# Main.net
KiCad netlist of a schematic drawn in Altium Designer
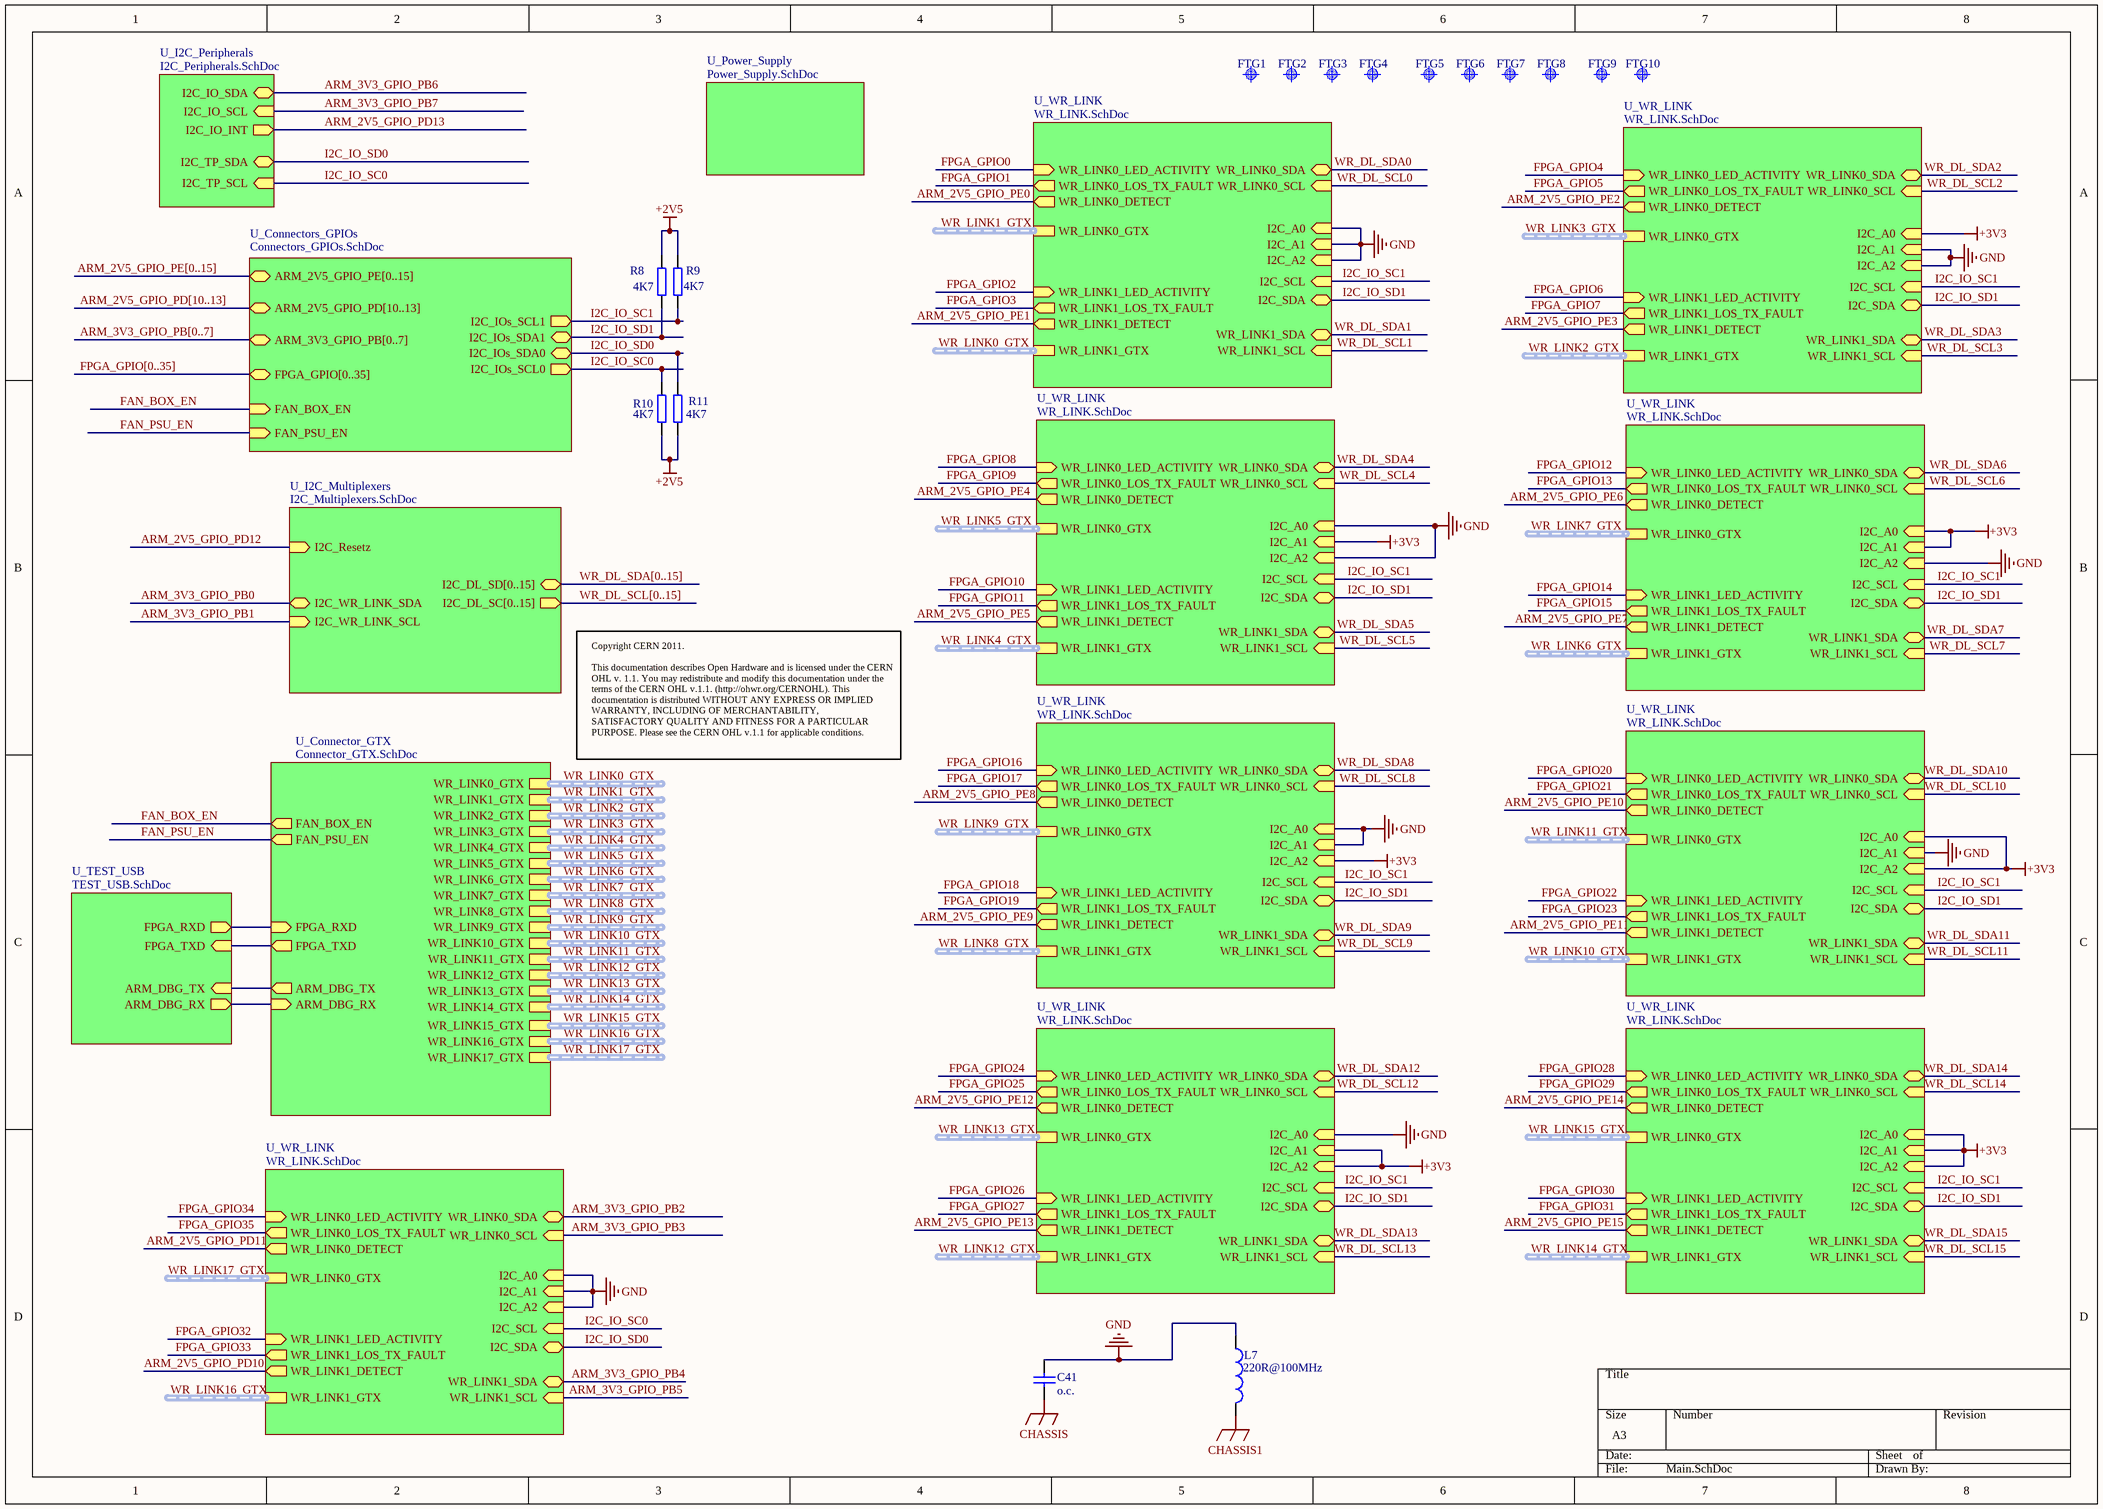
[diagram p0: Main.SchDoc]

(export (version "E")
  (design (tool "Eeschema 10.0.6"))
  (components
    (comp (ref "C41")
      (value "o.c.")
      (footprint "CC1608-0603")
      (description "Capacitor")
      (fields
        (field (name "TOLERANCE") "±10%")
        (field (name "VOLTAGE") "16V")
        (field (name "PUBLISHER") "Altium Limited")
      )
      (libsource (lib "wr_switch") (part "Cap"))
    )
    (comp (ref "FTG1")
      (value "Use only in PCB")
      (footprint "FIDUCIAL_TOP_S100-200")
      (description "Fiducial Target")
      (fields (field (name "PART NUMBER") "FIDUCIAL_TARGET_S100-200") (field (name "AUTHOR") "CERN DEM JLC"))
      (libsource (lib "wr_switch") (part "Fiducial Target"))
    )
    (comp (ref "FTG2")
      (value "Use only in PCB")
      (footprint "FIDUCIAL_TOP_S100-200")
      (description "Fiducial Target")
      (fields (field (name "PART NUMBER") "FIDUCIAL_TARGET_S100-200") (field (name "AUTHOR") "CERN DEM JLC"))
      (libsource (lib "wr_switch") (part "Fiducial Target"))
    )
    (comp (ref "FTG3")
      (value "Use only in PCB")
      (footprint "FIDUCIAL_TOP_S100-200")
      (description "Fiducial Target")
      (fields (field (name "PART NUMBER") "FIDUCIAL_TARGET_S100-200") (field (name "AUTHOR") "CERN DEM JLC"))
      (libsource (lib "wr_switch") (part "Fiducial Target"))
    )
    (comp (ref "FTG4")
      (value "Use only in PCB")
      (footprint "FIDUCIAL_TOP_S100-200")
      (description "Fiducial Target")
      (fields (field (name "PART NUMBER") "FIDUCIAL_TARGET_S100-200") (field (name "AUTHOR") "CERN DEM JLC"))
      (libsource (lib "wr_switch") (part "Fiducial Target"))
    )
    (comp (ref "FTG5")
      (value "Use only in PCB")
      (footprint "FIDUCIAL_TOP_S100-200")
      (description "Fiducial Target")
      (fields (field (name "PART NUMBER") "FIDUCIAL_TARGET_S100-200") (field (name "AUTHOR") "CERN DEM JLC"))
      (libsource (lib "wr_switch") (part "Fiducial Target"))
    )
    (comp (ref "FTG6")
      (value "Use only in PCB")
      (footprint "FIDUCIAL_TOP_S100-200")
      (description "Fiducial Target")
      (fields (field (name "PART NUMBER") "FIDUCIAL_TARGET_S100-200") (field (name "AUTHOR") "CERN DEM JLC"))
      (libsource (lib "wr_switch") (part "Fiducial Target"))
    )
    (comp (ref "FTG7")
      (value "Use only in PCB")
      (footprint "FIDUCIAL_TOP_S100-200")
      (description "Fiducial Target")
      (fields (field (name "PART NUMBER") "FIDUCIAL_TARGET_S100-200") (field (name "AUTHOR") "CERN DEM JLC"))
      (libsource (lib "wr_switch") (part "Fiducial Target"))
    )
    (comp (ref "FTG8")
      (value "Use only in PCB")
      (footprint "FIDUCIAL_TOP_S100-200")
      (description "Fiducial Target")
      (fields (field (name "PART NUMBER") "FIDUCIAL_TARGET_S100-200") (field (name "AUTHOR") "CERN DEM JLC"))
      (libsource (lib "wr_switch") (part "Fiducial Target"))
    )
    (comp (ref "FTG9")
      (value "Use only in PCB")
      (footprint "FIDUCIAL_TOP_S100-200")
      (description "Fiducial Target")
      (fields (field (name "PART NUMBER") "FIDUCIAL_TARGET_S100-200") (field (name "AUTHOR") "CERN DEM JLC"))
      (libsource (lib "wr_switch") (part "Fiducial Target"))
    )
    (comp (ref "FTG10")
      (value "Use only in PCB")
      (footprint "FIDUCIAL_TOP_S100-200")
      (description "Fiducial Target")
      (fields (field (name "PART NUMBER") "FIDUCIAL_TARGET_S100-200") (field (name "AUTHOR") "CERN DEM JLC"))
      (libsource (lib "wr_switch") (part "Fiducial Target"))
    )
    (comp (ref "L7")
      (value "220R@100MHz Ferrite Bead")
      (footprint "0603")
      (description "ferrite bead")
      (fields (field (name "IMPEDANCE") "220R@100MHz"))
      (libsource (lib "wr_switch") (part "L_FERRITE_BEAD"))
    )
    (comp (ref "R8")
      (value "4K7")
      (footprint "0603")
      (description "SMD Resistor")
      (fields (field (name "TOLERANCE") "±1%"))
      (libsource (lib "wr_switch") (part "RES_SMD"))
    )
    (comp (ref "R9")
      (value "4K7")
      (footprint "0603")
      (description "SMD Resistor")
      (fields (field (name "TOLERANCE") "±1%"))
      (libsource (lib "wr_switch") (part "RES_SMD"))
    )
    (comp (ref "R10")
      (value "4K7")
      (footprint "0603")
      (description "SMD Resistor")
      (fields (field (name "TOLERANCE") "±1%"))
      (libsource (lib "wr_switch") (part "RES_SMD"))
    )
    (comp (ref "R11")
      (value "4K7")
      (footprint "0603")
      (description "SMD Resistor")
      (fields (field (name "TOLERANCE") "±1%"))
      (libsource (lib "wr_switch") (part "RES_SMD"))
    )
  )
  (nets
    (net (code "19") (name "+2V5") (class "Default")
      (node (ref "R10") (pin "2") (pinfunction "2_2") (pintype "passive"))
      (node (ref "R11") (pin "1") (pinfunction "1_1") (pintype "passive"))
      (node (ref "R8") (pin "2") (pinfunction "2_2") (pintype "passive"))
      (node (ref "R9") (pin "1") (pinfunction "1_1") (pintype "passive"))
    )
    (net (code "101") (name "/I2C_IO_SC0") (class "Default")
      (node (ref "R10") (pin "1") (pinfunction "1_1") (pintype "passive"))
    )
    (net (code "102") (name "/I2C_IO_SC1") (class "Default")
      (node (ref "R9") (pin "2") (pinfunction "2_2") (pintype "passive"))
    )
    (net (code "103") (name "/I2C_IO_SD0") (class "Default")
      (node (ref "R11") (pin "2") (pinfunction "2_2") (pintype "passive"))
    )
    (net (code "104") (name "/I2C_IO_SD1") (class "Default")
      (node (ref "R8") (pin "1") (pinfunction "1_1") (pintype "passive"))
    )
    (net (code "184") (name "CHASSIS") (class "Default")
      (node (ref "C41") (pin "1") (pinfunction "1_1") (pintype "passive"))
    )
    (net (code "185") (name "CHASSIS1") (class "Default")
      (node (ref "L7") (pin "2") (pinfunction "2_2") (pintype "passive"))
    )
    (net (code "186") (name "GND") (class "Default")
      (node (ref "C41") (pin "2") (pinfunction "2_2") (pintype "passive"))
      (node (ref "L7") (pin "1") (pinfunction "1_1") (pintype "passive"))
    )
  )
)
